# Audio_in.net
KiCad netlist of a schematic drawn in Altium Designer
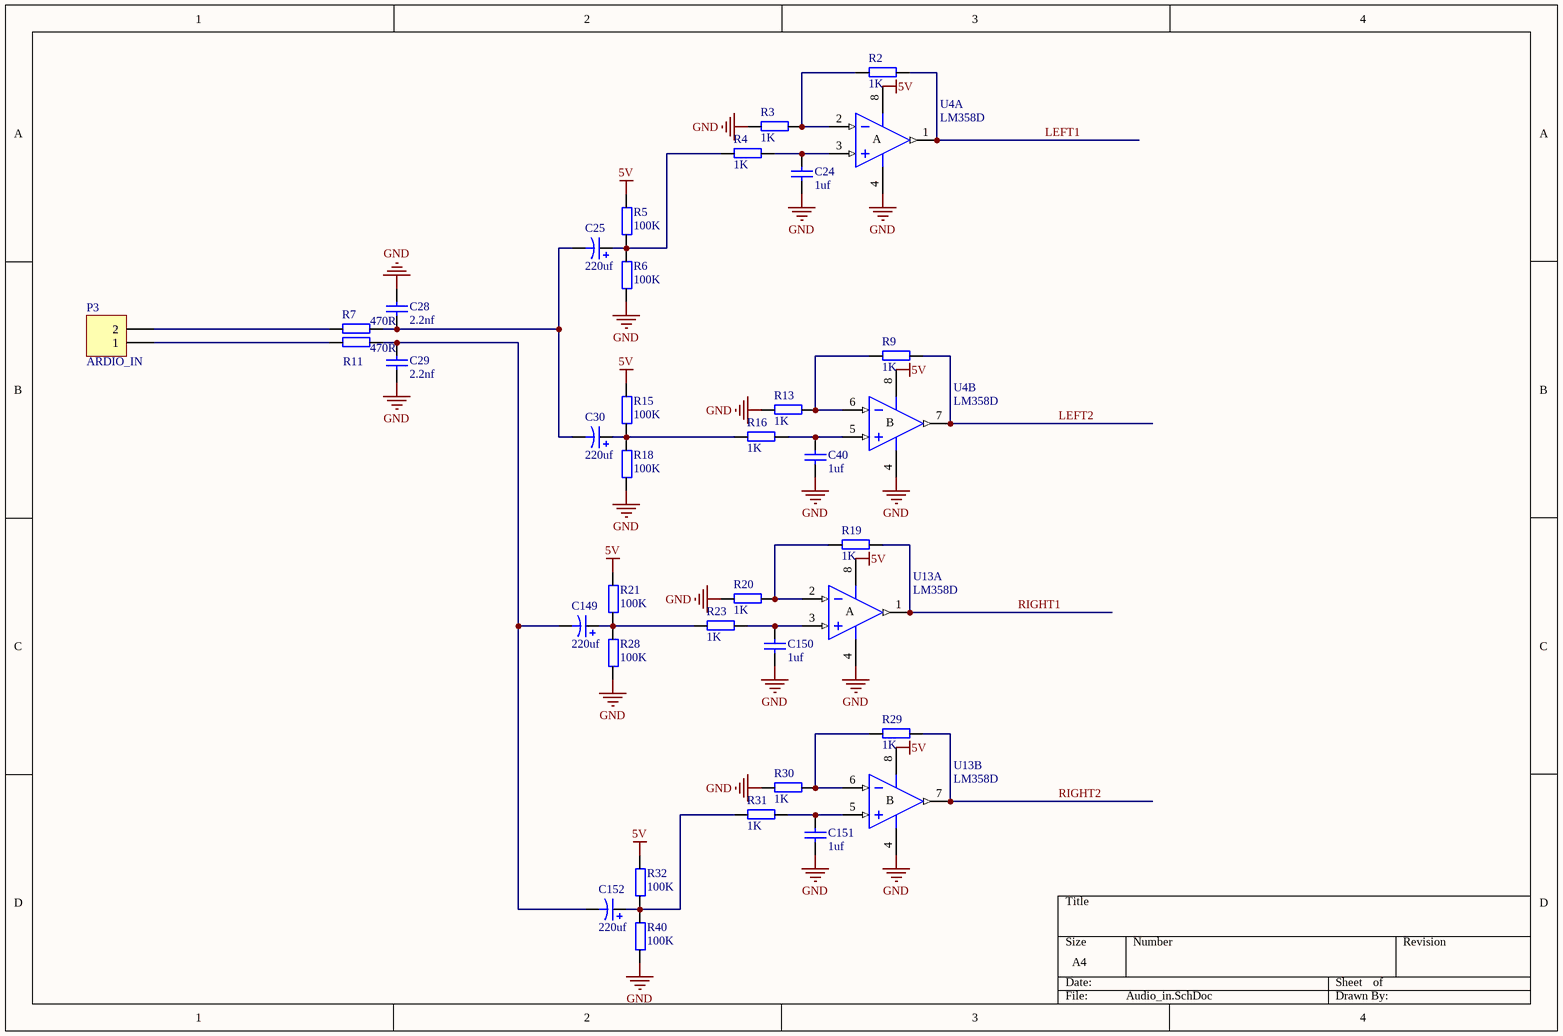
[diagram p0: Audio_in.SchDoc]

(export (version "E")
  (design (tool "Eeschema 10.0.6"))
  (components
    (comp (ref "C24")
      (value "1uf")
      (footprint "0805C")
      (description "Capacitor")
      (fields (field (name "PUBLISHER") "Altium Limited"))
      (libsource (lib "Miscellaneous Devices") (part "Cap"))
    )
    (comp (ref "C25")
      (value "220uf")
      (footprint "6032c")
      (description "Polarized Capacitor (Radial)")
      (fields (field (name "PUBLISHER") "Altium Limited"))
      (libsource (lib "Miscellaneous Devices") (part "Cap Pol1"))
    )
    (comp (ref "C28")
      (value "2.2nf")
      (footprint "0805C")
      (description "Capacitor")
      (fields (field (name "PUBLISHER") "Altium Limited"))
      (libsource (lib "Miscellaneous Devices") (part "Cap"))
    )
    (comp (ref "C29")
      (value "2.2nf")
      (footprint "0805C")
      (description "Capacitor")
      (fields (field (name "PUBLISHER") "Altium Limited"))
      (libsource (lib "Miscellaneous Devices") (part "Cap"))
    )
    (comp (ref "C30")
      (value "220uf")
      (footprint "6032c")
      (description "Polarized Capacitor (Radial)")
      (fields (field (name "PUBLISHER") "Altium Limited"))
      (libsource (lib "Miscellaneous Devices") (part "Cap Pol1"))
    )
    (comp (ref "C40")
      (value "1uf")
      (footprint "0805C")
      (description "Capacitor")
      (fields (field (name "PUBLISHER") "Altium Limited"))
      (libsource (lib "Miscellaneous Devices") (part "Cap"))
    )
    (comp (ref "C149")
      (value "220uf")
      (footprint "6032c")
      (description "Polarized Capacitor (Radial)")
      (fields (field (name "PUBLISHER") "Altium Limited"))
      (libsource (lib "Miscellaneous Devices") (part "Cap Pol1"))
    )
    (comp (ref "C150")
      (value "1uf")
      (footprint "0805C")
      (description "Capacitor")
      (fields (field (name "PUBLISHER") "Altium Limited"))
      (libsource (lib "Miscellaneous Devices") (part "Cap"))
    )
    (comp (ref "C151")
      (value "1uf")
      (footprint "0805C")
      (description "Capacitor")
      (fields (field (name "PUBLISHER") "Altium Limited"))
      (libsource (lib "Miscellaneous Devices") (part "Cap"))
    )
    (comp (ref "C152")
      (value "220uf")
      (footprint "6032c")
      (description "Polarized Capacitor (Radial)")
      (fields (field (name "PUBLISHER") "Altium Limited"))
      (libsource (lib "Miscellaneous Devices") (part "Cap Pol1"))
    )
    (comp (ref "P3")
      (value "ARDIO_IN")
      (footprint "耳机座")
      (description "Header, 2-Pin")
      (fields (field (name "PUBLISHER") "Altium Limited"))
      (libsource (lib "Miscellaneous Connectors") (part "Header 2"))
    )
    (comp (ref "R2") (value "1K") (footprint "0805R") (libsource (lib "ATK-VS1053 MP3") (part "R")))
    (comp (ref "R3") (value "1K") (footprint "0805R") (libsource (lib "ATK-VS1053 MP3") (part "R")))
    (comp (ref "R4") (value "1K") (footprint "0805R") (libsource (lib "ATK-VS1053 MP3") (part "R")))
    (comp (ref "R5") (value "100K") (footprint "0805R") (libsource (lib "ATK-VS1053 MP3") (part "R")))
    (comp (ref "R6") (value "100K") (footprint "0805R") (libsource (lib "ATK-VS1053 MP3") (part "R")))
    (comp (ref "R7") (value "470R") (footprint "0805R") (libsource (lib "ATK-VS1053 MP3") (part "R")))
    (comp (ref "R9") (value "1K") (footprint "0805R") (libsource (lib "ATK-VS1053 MP3") (part "R")))
    (comp (ref "R11") (value "470R") (footprint "0805R") (libsource (lib "ATK-VS1053 MP3") (part "R")))
    (comp (ref "R13") (value "1K") (footprint "0805R") (libsource (lib "ATK-VS1053 MP3") (part "R")))
    (comp (ref "R15") (value "100K") (footprint "0805R") (libsource (lib "ATK-VS1053 MP3") (part "R")))
    (comp (ref "R16") (value "1K") (footprint "0805R") (libsource (lib "ATK-VS1053 MP3") (part "R")))
    (comp (ref "R18") (value "100K") (footprint "0805R") (libsource (lib "ATK-VS1053 MP3") (part "R")))
    (comp (ref "R19") (value "1K") (footprint "0805R") (libsource (lib "ATK-VS1053 MP3") (part "R")))
    (comp (ref "R20") (value "1K") (footprint "0805R") (libsource (lib "ATK-VS1053 MP3") (part "R")))
    (comp (ref "R21") (value "100K") (footprint "0805R") (libsource (lib "ATK-VS1053 MP3") (part "R")))
    (comp (ref "R23") (value "1K") (footprint "0805R") (libsource (lib "ATK-VS1053 MP3") (part "R")))
    (comp (ref "R28") (value "100K") (footprint "0805R") (libsource (lib "ATK-VS1053 MP3") (part "R")))
    (comp (ref "R29") (value "1K") (footprint "0805R") (libsource (lib "ATK-VS1053 MP3") (part "R")))
    (comp (ref "R30") (value "1K") (footprint "0805R") (libsource (lib "ATK-VS1053 MP3") (part "R")))
    (comp (ref "R31") (value "1K") (footprint "0805R") (libsource (lib "ATK-VS1053 MP3") (part "R")))
    (comp (ref "R32") (value "100K") (footprint "0805R") (libsource (lib "ATK-VS1053 MP3") (part "R")))
    (comp (ref "R40") (value "100K") (footprint "0805R") (libsource (lib "ATK-VS1053 MP3") (part "R")))
    (comp (ref "U4")
      (value "LM358D")
      (footprint "D008_L")
      (description "Dual Operational Amplifier")
      (fields (field (name "PUBLISHER") "Altium Limited"))
      (libsource (lib "TI Operational Amplifier") (part "LM358D"))
    )
    (comp (ref "U13")
      (value "LM358D")
      (footprint "D008_L")
      (description "Dual Operational Amplifier")
      (fields (field (name "PUBLISHER") "Altium Limited"))
      (libsource (lib "TI Operational Amplifier") (part "LM358D"))
    )
  )
  (nets
    (net (code "1") (name "/LEFT1") (class "Default")
      (node (ref "R2") (pin "1") (pintype "passive"))
      (node (ref "U4") (pin "1") (pinfunction "OUT_1") (pintype "output"))
    )
    (net (code "2") (name "/LEFT2") (class "Default")
      (node (ref "R9") (pin "1") (pintype "passive"))
      (node (ref "U4") (pin "7") (pinfunction "OUT_7") (pintype "output"))
    )
    (net (code "3") (name "/RIGHT1") (class "Default")
      (node (ref "R19") (pin "1") (pintype "passive"))
      (node (ref "U13") (pin "1") (pinfunction "OUT_1") (pintype "output"))
    )
    (net (code "4") (name "/RIGHT2") (class "Default")
      (node (ref "R29") (pin "1") (pintype "passive"))
      (node (ref "U13") (pin "7") (pinfunction "OUT_7") (pintype "output"))
    )
    (net (code "5") (name "5V") (class "Default")
      (node (ref "R15") (pin "2") (pintype "passive"))
      (node (ref "R21") (pin "2") (pintype "passive"))
      (node (ref "R32") (pin "2") (pintype "passive"))
      (node (ref "R5") (pin "2") (pintype "passive"))
      (node (ref "U13") (pin "8") (pinfunction "V+_8") (pintype "power_in"))
      (node (ref "U4") (pin "8") (pinfunction "V+_8") (pintype "power_in"))
    )
    (net (code "6") (name "GND") (class "Default")
      (node (ref "C150") (pin "2") (pinfunction "2_2") (pintype "passive"))
      (node (ref "C151") (pin "2") (pinfunction "2_2") (pintype "passive"))
      (node (ref "C24") (pin "2") (pinfunction "2_2") (pintype "passive"))
      (node (ref "C28") (pin "1") (pinfunction "1_1") (pintype "passive"))
      (node (ref "C29") (pin "2") (pinfunction "2_2") (pintype "passive"))
      (node (ref "C40") (pin "2") (pinfunction "2_2") (pintype "passive"))
      (node (ref "R13") (pin "2") (pintype "passive"))
      (node (ref "R18") (pin "1") (pintype "passive"))
      (node (ref "R20") (pin "2") (pintype "passive"))
      (node (ref "R28") (pin "1") (pintype "passive"))
      (node (ref "R3") (pin "2") (pintype "passive"))
      (node (ref "R30") (pin "2") (pintype "passive"))
      (node (ref "R40") (pin "1") (pintype "passive"))
      (node (ref "R6") (pin "1") (pintype "passive"))
      (node (ref "U13") (pin "4") (pinfunction "V-_4") (pintype "power_in"))
      (node (ref "U4") (pin "4") (pinfunction "V-_4") (pintype "power_in"))
    )
    (net (code "7") (name "Net-(C25-Pad1)") (class "Default")
      (node (ref "C25") (pin "1") (pinfunction "1_1") (pintype "passive"))
      (node (ref "R4") (pin "2") (pintype "passive"))
      (node (ref "R5") (pin "1") (pintype "passive"))
      (node (ref "R6") (pin "2") (pintype "passive"))
    )
    (net (code "8") (name "Net-(C25-Pad2)") (class "Default")
      (node (ref "C25") (pin "2") (pinfunction "2_2") (pintype "passive"))
      (node (ref "C28") (pin "2") (pinfunction "2_2") (pintype "passive"))
      (node (ref "C30") (pin "2") (pinfunction "2_2") (pintype "passive"))
      (node (ref "R7") (pin "1") (pintype "passive"))
    )
    (net (code "9") (name "Net-(C30-Pad1)") (class "Default")
      (node (ref "C30") (pin "1") (pinfunction "1_1") (pintype "passive"))
      (node (ref "R15") (pin "1") (pintype "passive"))
      (node (ref "R16") (pin "2") (pintype "passive"))
      (node (ref "R18") (pin "2") (pintype "passive"))
    )
    (net (code "10") (name "Net-(C149-Pad1)") (class "Default")
      (node (ref "C149") (pin "1") (pinfunction "1_1") (pintype "passive"))
      (node (ref "R21") (pin "1") (pintype "passive"))
      (node (ref "R23") (pin "2") (pintype "passive"))
      (node (ref "R28") (pin "2") (pintype "passive"))
    )
    (net (code "11") (name "Net-(C149-Pad2)") (class "Default")
      (node (ref "C149") (pin "2") (pinfunction "2_2") (pintype "passive"))
      (node (ref "C152") (pin "2") (pinfunction "2_2") (pintype "passive"))
      (node (ref "C29") (pin "1") (pinfunction "1_1") (pintype "passive"))
      (node (ref "R11") (pin "1") (pintype "passive"))
    )
    (net (code "12") (name "Net-(C152-Pad1)") (class "Default")
      (node (ref "C152") (pin "1") (pinfunction "1_1") (pintype "passive"))
      (node (ref "R31") (pin "2") (pintype "passive"))
      (node (ref "R32") (pin "1") (pintype "passive"))
      (node (ref "R40") (pin "2") (pintype "passive"))
    )
    (net (code "13") (name "Net-(P3-Pad1)") (class "Default")
      (node (ref "P3") (pin "1") (pinfunction "1_1") (pintype "passive"))
      (node (ref "R11") (pin "2") (pintype "passive"))
    )
    (net (code "14") (name "Net-(P3-Pad2)") (class "Default")
      (node (ref "P3") (pin "2") (pinfunction "2_2") (pintype "passive"))
      (node (ref "R7") (pin "2") (pintype "passive"))
    )
    (net (code "15") (name "Net-(U4A-IN+)") (class "Default")
      (node (ref "C24") (pin "1") (pinfunction "1_1") (pintype "passive"))
      (node (ref "R4") (pin "1") (pintype "passive"))
      (node (ref "U4") (pin "3") (pinfunction "IN+_3") (pintype "input"))
    )
    (net (code "16") (name "Net-(U4A-IN-)") (class "Default")
      (node (ref "R2") (pin "2") (pintype "passive"))
      (node (ref "R3") (pin "1") (pintype "passive"))
      (node (ref "U4") (pin "2") (pinfunction "IN-_2") (pintype "input"))
    )
    (net (code "17") (name "Net-(U4B-IN+)") (class "Default")
      (node (ref "C40") (pin "1") (pinfunction "1_1") (pintype "passive"))
      (node (ref "R16") (pin "1") (pintype "passive"))
      (node (ref "U4") (pin "5") (pinfunction "IN+_5") (pintype "input"))
    )
    (net (code "18") (name "Net-(U4B-IN-)") (class "Default")
      (node (ref "R13") (pin "1") (pintype "passive"))
      (node (ref "R9") (pin "2") (pintype "passive"))
      (node (ref "U4") (pin "6") (pinfunction "IN-_6") (pintype "input"))
    )
    (net (code "19") (name "Net-(U13A-IN+)") (class "Default")
      (node (ref "C150") (pin "1") (pinfunction "1_1") (pintype "passive"))
      (node (ref "R23") (pin "1") (pintype "passive"))
      (node (ref "U13") (pin "3") (pinfunction "IN+_3") (pintype "input"))
    )
    (net (code "20") (name "Net-(U13A-IN-)") (class "Default")
      (node (ref "R19") (pin "2") (pintype "passive"))
      (node (ref "R20") (pin "1") (pintype "passive"))
      (node (ref "U13") (pin "2") (pinfunction "IN-_2") (pintype "input"))
    )
    (net (code "21") (name "Net-(U13B-IN+)") (class "Default")
      (node (ref "C151") (pin "1") (pinfunction "1_1") (pintype "passive"))
      (node (ref "R31") (pin "1") (pintype "passive"))
      (node (ref "U13") (pin "5") (pinfunction "IN+_5") (pintype "input"))
    )
    (net (code "22") (name "Net-(U13B-IN-)") (class "Default")
      (node (ref "R29") (pin "2") (pintype "passive"))
      (node (ref "R30") (pin "1") (pintype "passive"))
      (node (ref "U13") (pin "6") (pinfunction "IN-_6") (pintype "input"))
    )
  )
)
